# Batt_Charger.net
KiCad netlist of a schematic drawn in Altium Designer
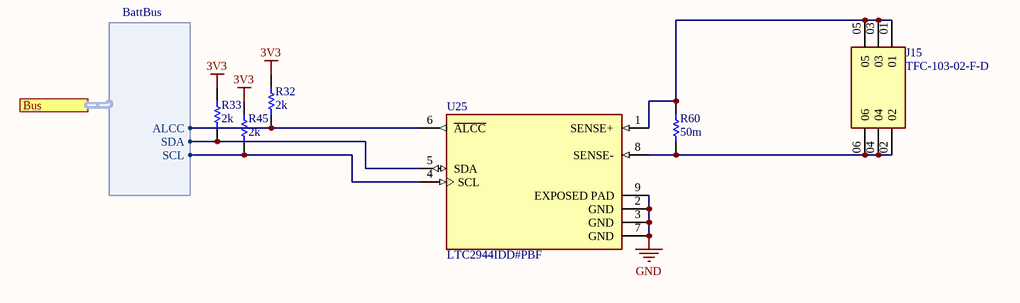
[diagram p0: Batt_Charger.SchDoc]

(export (version "E")
  (design (tool "Eeschema 10.0.6"))
  (components
    (comp (ref "J15")
      (value "TFC-103-02-F-D")
      (footprint "Arturo_Approved:SAMTEC_TFC-103-02-F-D")
      (fields (field (name "MF") "Samtec"))
      (libsource (lib "Arturo_Approved") (part "TFC-103-02-F-D"))
    )
    (comp (ref "R32")
      (value "2k")
      (footprint "0402_Res")
      (description "1K 1% 1/4W")
      (libsource (lib "Arturo_Approved") (part "RNCP0805FTD1K00"))
    )
    (comp (ref "R33")
      (value "2k")
      (footprint "0402_Res")
      (description "1K 1% 1/4W")
      (libsource (lib "Arturo_Approved") (part "RNCP0805FTD1K00"))
    )
    (comp (ref "R45")
      (value "2k")
      (footprint "0402_Res")
      (description "1K 1% 1/4W")
      (libsource (lib "Arturo_Approved") (part "RNCP0805FTD1K00"))
    )
    (comp (ref "R60")
      (value "50m")
      (footprint "STD_0805_R")
      (description "1K 1% 1/4W")
      (libsource (lib "Arturo_Approved") (part "RNCP0805FTD1K00"))
    )
    (comp (ref "U25")
      (value "LTC2944IDD#PBF")
      (footprint "FP-DD-8-05-08-1698-MFG")
      (description "IC BATTERY GAS GAUGE I2C 8DFN")
      (fields
        (field (name "MANUFACTURER") "Analog Devices")
        (field (name "OCTOPART") "https://octopart.com/ltc2944idd%23pbf-analog+devices-88318751")
      )
      (libsource (lib "Altium Content Vault") (part "2d588ed73019e1f06a7b641f7005350"))
    )
  )
  (nets
    (net (code "3") (name "3V3") (class "Default")
      (node (ref "R32") (pin "2") (pinfunction "2_2") (pintype "passive"))
      (node (ref "R33") (pin "2") (pinfunction "2_2") (pintype "passive"))
      (node (ref "R45") (pin "2") (pinfunction "2_2") (pintype "passive"))
    )
    (net (code "4") (name "GND") (class "Default")
      (node (ref "U25") (pin "2") (pinfunction "GND_2") (pintype "power_in"))
      (node (ref "U25") (pin "3") (pinfunction "GND_3") (pintype "power_in"))
      (node (ref "U25") (pin "7") (pinfunction "GND_7") (pintype "power_in"))
      (node (ref "U25") (pin "9") (pinfunction "EXPOSED_PAD_9") (pintype "power_in"))
    )
    (net (code "5") (name "Net-(U25-SCL)") (class "Default")
      (node (ref "R45") (pin "1") (pinfunction "1_1") (pintype "passive"))
      (node (ref "U25") (pin "4") (pinfunction "SCL_4") (pintype "input"))
    )
    (net (code "6") (name "Net-(U25-SDA)") (class "Default")
      (node (ref "R33") (pin "1") (pinfunction "1_1") (pintype "passive"))
      (node (ref "U25") (pin "5") (pinfunction "SDA_5") (pintype "bidirectional"))
    )
    (net (code "7") (name "Net-(U25-SENSE+)") (class "Default")
      (node (ref "J15") (pin "01") (pinfunction "01_01") (pintype "passive"))
      (node (ref "J15") (pin "03") (pinfunction "03_03") (pintype "passive"))
      (node (ref "J15") (pin "05") (pinfunction "05_05") (pintype "passive"))
      (node (ref "R60") (pin "2") (pinfunction "2_2") (pintype "passive"))
      (node (ref "U25") (pin "1") (pinfunction "SENSE+_1") (pintype "input"))
    )
    (net (code "8") (name "Net-(U25-SENSE-)") (class "Default")
      (node (ref "J15") (pin "02") (pinfunction "02_02") (pintype "passive"))
      (node (ref "J15") (pin "04") (pinfunction "04_04") (pintype "passive"))
      (node (ref "J15") (pin "06") (pinfunction "06_06") (pintype "passive"))
      (node (ref "R60") (pin "1") (pinfunction "1_1") (pintype "passive"))
      (node (ref "U25") (pin "8") (pinfunction "SENSE-_8") (pintype "input"))
    )
    (net (code "9") (name "Net-(U25-~{ALCC})") (class "Default")
      (node (ref "R32") (pin "1") (pinfunction "1_1") (pintype "passive"))
      (node (ref "U25") (pin "6") (pinfunction "~{ALCC}_6") (pintype "output"))
    )
  )
)
